# Stepper_Motor_Driver.net
KiCad netlist of a schematic drawn in Altium Designer
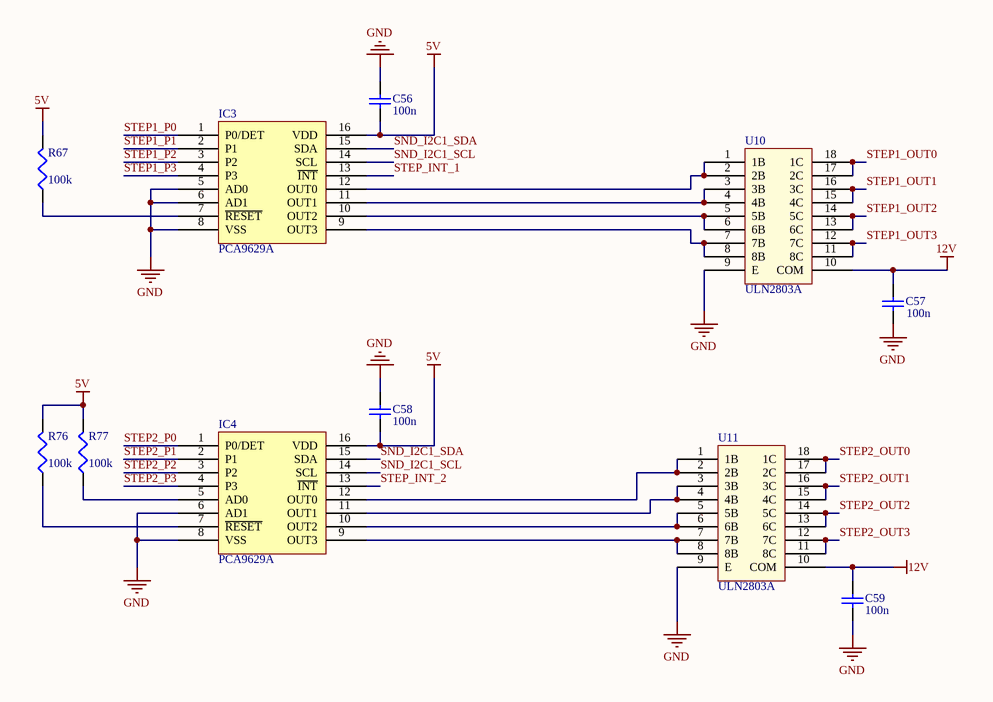
[diagram p0: Stepper Motor Driver.SchDoc]

(export (version "E")
  (design (tool "Eeschema 10.0.6"))
  (components
    (comp (ref "C56")
      (value "100n")
      (footprint "0805C-GENERIC")
      (description "Capacitor (Semiconductor SIM Model)")
      (fields (field (name "Comment") "Cap Semi") (field (name "PUBLISHER") "Altium Limited"))
      (libsource (lib "Miscellaneous Devices") (part "Cap Semi"))
    )
    (comp (ref "C57")
      (value "100n")
      (footprint "0805C-GENERIC")
      (description "Capacitor (Semiconductor SIM Model)")
      (fields (field (name "Comment") "Cap Semi") (field (name "PUBLISHER") "Altium Limited"))
      (libsource (lib "Miscellaneous Devices") (part "Cap Semi"))
    )
    (comp (ref "C58")
      (value "100n")
      (footprint "0805C-GENERIC")
      (description "Capacitor (Semiconductor SIM Model)")
      (fields (field (name "Comment") "Cap Semi") (field (name "PUBLISHER") "Altium Limited"))
      (libsource (lib "Miscellaneous Devices") (part "Cap Semi"))
    )
    (comp (ref "C59")
      (value "100n")
      (footprint "0805C-GENERIC")
      (description "Capacitor (Semiconductor SIM Model)")
      (fields (field (name "Comment") "Cap Semi") (field (name "PUBLISHER") "Altium Limited"))
      (libsource (lib "Miscellaneous Devices") (part "Cap Semi"))
    )
    (comp (ref "IC3")
      (value "PCA9629A")
      (footprint "TSSOP16")
      (description "Fm+ I2C-bus advanced stepper motor controller")
      (libsource (lib "NXP") (part "PCA9629A"))
    )
    (comp (ref "IC4")
      (value "PCA9629A")
      (footprint "TSSOP16")
      (description "Fm+ I2C-bus advanced stepper motor controller")
      (libsource (lib "NXP") (part "PCA9629A"))
    )
    (comp (ref "R67")
      (value "100k")
      (footprint "0805R-GENERIC")
      (description "Resistor")
      (fields (field (name "Comment") "Res3") (field (name "PUBLISHER") "Altium Limited"))
      (libsource (lib "Miscellaneous Devices") (part "Res3"))
    )
    (comp (ref "R76")
      (value "100k")
      (footprint "0805R-GENERIC")
      (description "Resistor")
      (fields (field (name "Comment") "Res3") (field (name "PUBLISHER") "Altium Limited"))
      (libsource (lib "Miscellaneous Devices") (part "Res3"))
    )
    (comp (ref "R77")
      (value "100k")
      (footprint "0805R-GENERIC")
      (description "Resistor")
      (fields (field (name "Comment") "Res3") (field (name "PUBLISHER") "Altium Limited"))
      (libsource (lib "Miscellaneous Devices") (part "Res3"))
    )
    (comp (ref "U10")
      (value "ULN2803A")
      (footprint "SOIC18")
      (libsource (lib "Texas_Instruments") (part "ULN2803A"))
    )
    (comp (ref "U11")
      (value "ULN2803A")
      (footprint "SOIC18")
      (libsource (lib "Texas_Instruments") (part "ULN2803A"))
    )
  )
  (nets
    (net (code "1") (name "/SND_I2C1_SCL") (class "Default")
      (node (ref "IC3") (pin "14") (pinfunction "SCL_14") (pintype "passive"))
      (node (ref "IC4") (pin "14") (pinfunction "SCL_14") (pintype "passive"))
    )
    (net (code "2") (name "/SND_I2C1_SDA") (class "Default")
      (node (ref "IC3") (pin "15") (pinfunction "SDA_15") (pintype "passive"))
      (node (ref "IC4") (pin "15") (pinfunction "SDA_15") (pintype "passive"))
    )
    (net (code "3") (name "/STEP1_OUT0") (class "Default")
      (node (ref "U10") (pin "17") (pinfunction "2C_17") (pintype "passive"))
      (node (ref "U10") (pin "18") (pinfunction "1C_18") (pintype "passive"))
    )
    (net (code "4") (name "/STEP1_OUT1") (class "Default")
      (node (ref "U10") (pin "15") (pinfunction "4C_15") (pintype "passive"))
      (node (ref "U10") (pin "16") (pinfunction "3C_16") (pintype "passive"))
    )
    (net (code "5") (name "/STEP1_OUT2") (class "Default")
      (node (ref "U10") (pin "13") (pinfunction "6C_13") (pintype "passive"))
      (node (ref "U10") (pin "14") (pinfunction "5C_14") (pintype "passive"))
    )
    (net (code "6") (name "/STEP1_OUT3") (class "Default")
      (node (ref "U10") (pin "11") (pinfunction "8C_11") (pintype "passive"))
      (node (ref "U10") (pin "12") (pinfunction "7C_12") (pintype "passive"))
    )
    (net (code "7") (name "/STEP1_P0") (class "Default")
      (node (ref "IC3") (pin "1") (pinfunction "P0/DET_1") (pintype "passive"))
    )
    (net (code "8") (name "/STEP1_P1") (class "Default")
      (node (ref "IC3") (pin "2") (pinfunction "P1_2") (pintype "passive"))
    )
    (net (code "9") (name "/STEP1_P2") (class "Default")
      (node (ref "IC3") (pin "3") (pinfunction "P2_3") (pintype "passive"))
    )
    (net (code "10") (name "/STEP1_P3") (class "Default")
      (node (ref "IC3") (pin "4") (pinfunction "P3_4") (pintype "passive"))
    )
    (net (code "11") (name "/STEP2_OUT0") (class "Default")
      (node (ref "U11") (pin "17") (pinfunction "2C_17") (pintype "passive"))
      (node (ref "U11") (pin "18") (pinfunction "1C_18") (pintype "passive"))
    )
    (net (code "12") (name "/STEP2_OUT1") (class "Default")
      (node (ref "U11") (pin "15") (pinfunction "4C_15") (pintype "passive"))
      (node (ref "U11") (pin "16") (pinfunction "3C_16") (pintype "passive"))
    )
    (net (code "13") (name "/STEP2_OUT2") (class "Default")
      (node (ref "U11") (pin "13") (pinfunction "6C_13") (pintype "passive"))
      (node (ref "U11") (pin "14") (pinfunction "5C_14") (pintype "passive"))
    )
    (net (code "14") (name "/STEP2_OUT3") (class "Default")
      (node (ref "U11") (pin "11") (pinfunction "8C_11") (pintype "passive"))
      (node (ref "U11") (pin "12") (pinfunction "7C_12") (pintype "passive"))
    )
    (net (code "15") (name "/STEP2_P0") (class "Default")
      (node (ref "IC4") (pin "1") (pinfunction "P0/DET_1") (pintype "passive"))
    )
    (net (code "16") (name "/STEP2_P1") (class "Default")
      (node (ref "IC4") (pin "2") (pinfunction "P1_2") (pintype "passive"))
    )
    (net (code "17") (name "/STEP2_P2") (class "Default")
      (node (ref "IC4") (pin "3") (pinfunction "P2_3") (pintype "passive"))
    )
    (net (code "18") (name "/STEP2_P3") (class "Default")
      (node (ref "IC4") (pin "4") (pinfunction "P3_4") (pintype "passive"))
    )
    (net (code "19") (name "/STEP_INT_1") (class "Default")
      (node (ref "IC3") (pin "13") (pinfunction "~{INT}_13") (pintype "passive"))
    )
    (net (code "20") (name "/STEP_INT_2") (class "Default")
      (node (ref "IC4") (pin "13") (pinfunction "~{INT}_13") (pintype "passive"))
    )
    (net (code "21") (name "5V") (class "Default")
      (node (ref "C56") (pin "1") (pinfunction "1_1") (pintype "passive"))
      (node (ref "C58") (pin "1") (pinfunction "1_1") (pintype "passive"))
      (node (ref "IC3") (pin "16") (pinfunction "VDD_16") (pintype "passive"))
      (node (ref "IC4") (pin "16") (pinfunction "VDD_16") (pintype "passive"))
      (node (ref "R67") (pin "2") (pinfunction "2_2") (pintype "passive"))
      (node (ref "R76") (pin "2") (pinfunction "2_2") (pintype "passive"))
      (node (ref "R77") (pin "2") (pinfunction "2_2") (pintype "passive"))
    )
    (net (code "22") (name "12V") (class "Default")
      (node (ref "C57") (pin "2") (pinfunction "2_2") (pintype "passive"))
      (node (ref "C59") (pin "2") (pinfunction "2_2") (pintype "passive"))
      (node (ref "U10") (pin "10") (pinfunction "COM_10") (pintype "passive"))
      (node (ref "U11") (pin "10") (pinfunction "COM_10") (pintype "passive"))
    )
    (net (code "23") (name "GND") (class "Default")
      (node (ref "C56") (pin "2") (pinfunction "2_2") (pintype "passive"))
      (node (ref "C57") (pin "1") (pinfunction "1_1") (pintype "passive"))
      (node (ref "C58") (pin "2") (pinfunction "2_2") (pintype "passive"))
      (node (ref "C59") (pin "1") (pinfunction "1_1") (pintype "passive"))
      (node (ref "IC3") (pin "5") (pinfunction "AD0_5") (pintype "passive"))
      (node (ref "IC3") (pin "6") (pinfunction "AD1_6") (pintype "passive"))
      (node (ref "IC3") (pin "8") (pinfunction "VSS_8") (pintype "passive"))
      (node (ref "IC4") (pin "6") (pinfunction "AD1_6") (pintype "passive"))
      (node (ref "IC4") (pin "8") (pinfunction "VSS_8") (pintype "passive"))
      (node (ref "U10") (pin "9") (pinfunction "E_9") (pintype "passive"))
      (node (ref "U11") (pin "9") (pinfunction "E_9") (pintype "passive"))
    )
    (net (code "24") (name "Net-(IC3-OUT0)") (class "Default")
      (node (ref "IC3") (pin "12") (pinfunction "OUT0_12") (pintype "passive"))
      (node (ref "U10") (pin "1") (pinfunction "1B_1") (pintype "passive"))
      (node (ref "U10") (pin "2") (pinfunction "2B_2") (pintype "passive"))
    )
    (net (code "25") (name "Net-(IC3-OUT1)") (class "Default")
      (node (ref "IC3") (pin "11") (pinfunction "OUT1_11") (pintype "passive"))
      (node (ref "U10") (pin "3") (pinfunction "3B_3") (pintype "passive"))
      (node (ref "U10") (pin "4") (pinfunction "4B_4") (pintype "passive"))
    )
    (net (code "26") (name "Net-(IC3-OUT2)") (class "Default")
      (node (ref "IC3") (pin "10") (pinfunction "OUT2_10") (pintype "passive"))
      (node (ref "U10") (pin "5") (pinfunction "5B_5") (pintype "passive"))
      (node (ref "U10") (pin "6") (pinfunction "6B_6") (pintype "passive"))
    )
    (net (code "27") (name "Net-(IC3-OUT3)") (class "Default")
      (node (ref "IC3") (pin "9") (pinfunction "OUT3_9") (pintype "passive"))
      (node (ref "U10") (pin "7") (pinfunction "7B_7") (pintype "passive"))
      (node (ref "U10") (pin "8") (pinfunction "8B_8") (pintype "passive"))
    )
    (net (code "28") (name "Net-(IC3-~{RESET})") (class "Default")
      (node (ref "IC3") (pin "7") (pinfunction "~{RESET}_7") (pintype "passive"))
      (node (ref "R67") (pin "1") (pinfunction "1_1") (pintype "passive"))
    )
    (net (code "29") (name "Net-(IC4-AD0)") (class "Default")
      (node (ref "IC4") (pin "5") (pinfunction "AD0_5") (pintype "passive"))
      (node (ref "R77") (pin "1") (pinfunction "1_1") (pintype "passive"))
    )
    (net (code "30") (name "Net-(IC4-OUT0)") (class "Default")
      (node (ref "IC4") (pin "12") (pinfunction "OUT0_12") (pintype "passive"))
      (node (ref "U11") (pin "1") (pinfunction "1B_1") (pintype "passive"))
      (node (ref "U11") (pin "2") (pinfunction "2B_2") (pintype "passive"))
    )
    (net (code "31") (name "Net-(IC4-OUT1)") (class "Default")
      (node (ref "IC4") (pin "11") (pinfunction "OUT1_11") (pintype "passive"))
      (node (ref "U11") (pin "3") (pinfunction "3B_3") (pintype "passive"))
      (node (ref "U11") (pin "4") (pinfunction "4B_4") (pintype "passive"))
    )
    (net (code "32") (name "Net-(IC4-OUT2)") (class "Default")
      (node (ref "IC4") (pin "10") (pinfunction "OUT2_10") (pintype "passive"))
      (node (ref "U11") (pin "5") (pinfunction "5B_5") (pintype "passive"))
      (node (ref "U11") (pin "6") (pinfunction "6B_6") (pintype "passive"))
    )
    (net (code "33") (name "Net-(IC4-OUT3)") (class "Default")
      (node (ref "IC4") (pin "9") (pinfunction "OUT3_9") (pintype "passive"))
      (node (ref "U11") (pin "7") (pinfunction "7B_7") (pintype "passive"))
      (node (ref "U11") (pin "8") (pinfunction "8B_8") (pintype "passive"))
    )
    (net (code "34") (name "Net-(IC4-~{RESET})") (class "Default")
      (node (ref "IC4") (pin "7") (pinfunction "~{RESET}_7") (pintype "passive"))
      (node (ref "R76") (pin "1") (pinfunction "1_1") (pintype "passive"))
    )
  )
)
